# Dual_Drive_4.net
KiCad netlist of a schematic drawn in EAGLE
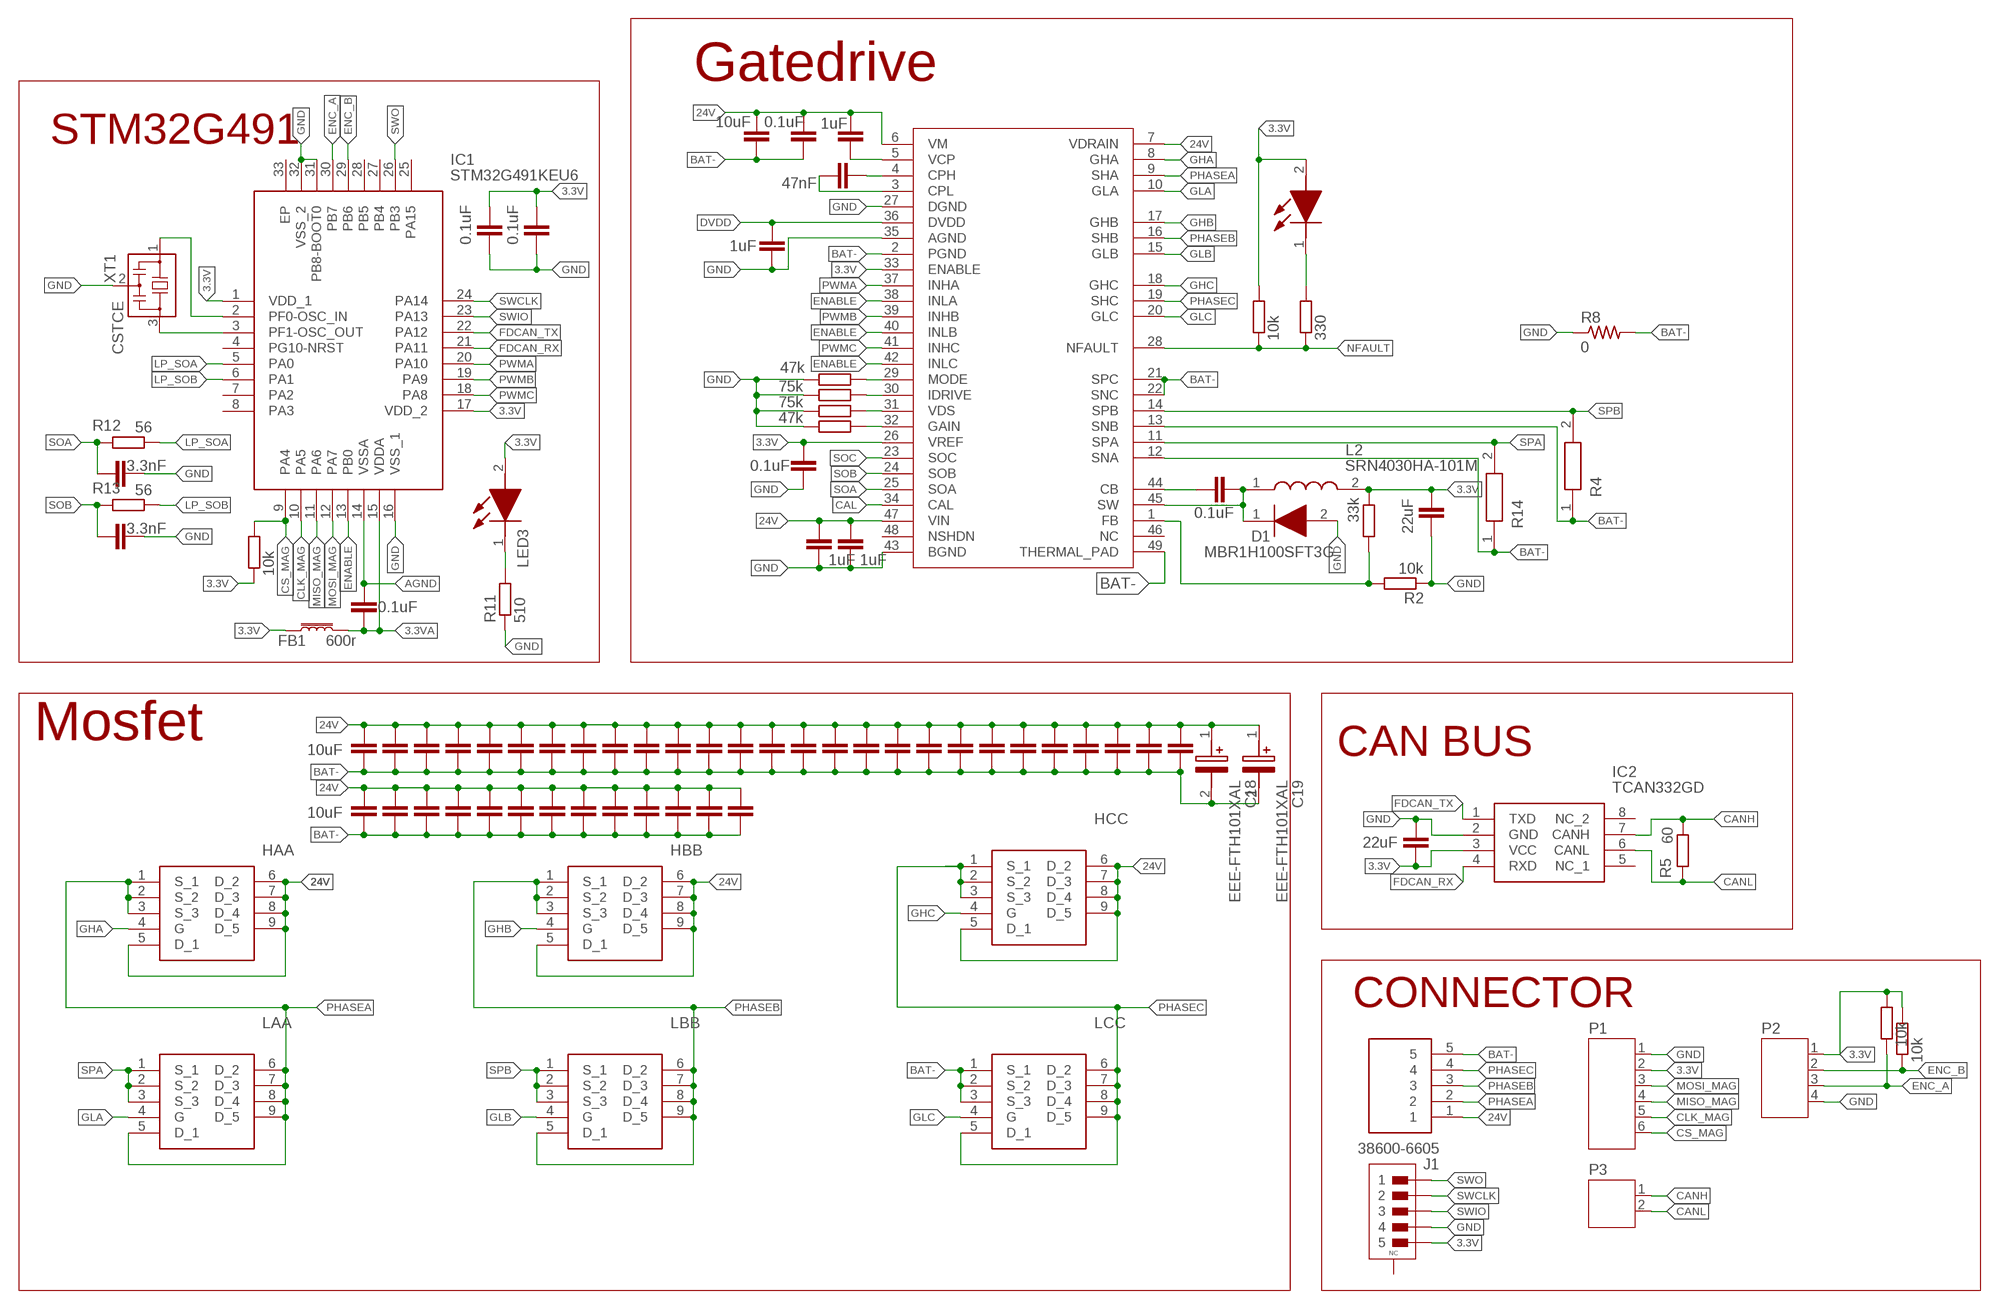
[diagram p0: schematic, sheet 1]

(export (version "E")
  (design (tool "Eeschema 10.0.6"))
  (components
    (comp (ref "C1")
      (value "3.3nF")
      (footprint "eagle-import:C0603")
      (libsource (lib "eagle-import") (part "rcl_334_C-EUC0603"))
    )
    (comp (ref "C2")
      (value "3.3nF")
      (footprint "eagle-import:C0603")
      (libsource (lib "eagle-import") (part "rcl_334_C-EUC0603"))
    )
    (comp (ref "C3")
      (value "10uF")
      (footprint "eagle-import:C1206")
      (libsource (lib "eagle-import") (part "C-EU1206C1206"))
    )
    (comp (ref "C4")
      (value "22uF")
      (footprint "eagle-import:C0603")
      (libsource (lib "eagle-import") (part "C-EUC0603"))
    )
    (comp (ref "C5")
      (value "10uF")
      (footprint "eagle-import:C1206")
      (libsource (lib "eagle-import") (part "C-EU1206C1206"))
    )
    (comp (ref "C6")
      (value "10uF")
      (footprint "eagle-import:C1206")
      (libsource (lib "eagle-import") (part "C-EU1206C1206"))
    )
    (comp (ref "C7")
      (value "10uF")
      (footprint "eagle-import:C1206")
      (libsource (lib "eagle-import") (part "C-EU1206C1206"))
    )
    (comp (ref "C8")
      (value "10uF")
      (footprint "eagle-import:C1206")
      (libsource (lib "eagle-import") (part "C-EU1206C1206"))
    )
    (comp (ref "C9")
      (value "10uF")
      (footprint "eagle-import:C1206")
      (libsource (lib "eagle-import") (part "C-EU1206C1206"))
    )
    (comp (ref "C10")
      (value "0.1uF")
      (footprint "eagle-import:C1206")
      (libsource (lib "eagle-import") (part "C-EU1206C1206"))
    )
    (comp (ref "C11")
      (value "1uF")
      (footprint "eagle-import:C0603")
      (libsource (lib "eagle-import") (part "C-EUC0603"))
    )
    (comp (ref "C12")
      (value "10uF")
      (footprint "eagle-import:C1206")
      (libsource (lib "eagle-import") (part "C-EU1206C1206"))
    )
    (comp (ref "C13")
      (value "0.1uF")
      (footprint "eagle-import:C0603")
      (libsource (lib "eagle-import") (part "C-EUC0603"))
    )
    (comp (ref "C14")
      (value "1uF")
      (footprint "eagle-import:C0603")
      (libsource (lib "eagle-import") (part "C-EUC0603"))
    )
    (comp (ref "C15")
      (value "0.1uF")
      (footprint "eagle-import:C0603")
      (libsource (lib "eagle-import") (part "C-EUC0603"))
    )
    (comp (ref "C16")
      (value "10uF")
      (footprint "eagle-import:C1206")
      (libsource (lib "eagle-import") (part "C-EU1206C1206"))
    )
    (comp (ref "C17")
      (value "10uF")
      (footprint "eagle-import:C1206")
      (libsource (lib "eagle-import") (part "C-EU1206C1206"))
    )
    (comp (ref "C18")
      (value "EEE-FTH101XAL")
      (footprint "eagle-import:EEEHP1H4R7P")
      (fields (field (name "MOUSER_PART_NUMBER") "667-EEE-FTH101XAL"))
      (libsource (lib "eagle-import") (part "EEE-FTH101XAL"))
    )
    (comp (ref "C19")
      (value "EEE-FTH101XAL")
      (footprint "eagle-import:EEEHP1H4R7P")
      (fields (field (name "MOUSER_PART_NUMBER") "667-EEE-FTH101XAL"))
      (libsource (lib "eagle-import") (part "EEE-FTH101XAL"))
    )
    (comp (ref "C20")
      (value "10uF")
      (footprint "eagle-import:C1206")
      (libsource (lib "eagle-import") (part "C-EU1206C1206"))
    )
    (comp (ref "C21")
      (value "10uF")
      (footprint "eagle-import:C1206")
      (libsource (lib "eagle-import") (part "C-EU1206C1206"))
    )
    (comp (ref "C22")
      (value "10uF")
      (footprint "eagle-import:C1206")
      (libsource (lib "eagle-import") (part "C-EU1206C1206"))
    )
    (comp (ref "C23")
      (value "10uF")
      (footprint "eagle-import:C1206")
      (libsource (lib "eagle-import") (part "C-EU1206C1206"))
    )
    (comp (ref "C24")
      (value "10uF")
      (footprint "eagle-import:C1206")
      (libsource (lib "eagle-import") (part "C-EU1206C1206"))
    )
    (comp (ref "C25")
      (value "10uF")
      (footprint "eagle-import:C1206")
      (libsource (lib "eagle-import") (part "C-EU1206C1206"))
    )
    (comp (ref "C26")
      (value "0.1uF")
      (footprint "eagle-import:C0603")
      (libsource (lib "eagle-import") (part "rcl_334_C-EUC0603"))
    )
    (comp (ref "C27")
      (value "0.1uF")
      (footprint "eagle-import:C0603")
      (libsource (lib "eagle-import") (part "rcl_334_C-EUC0603"))
    )
    (comp (ref "C28")
      (value "10uF")
      (footprint "eagle-import:C1206")
      (libsource (lib "eagle-import") (part "C-EU1206C1206"))
    )
    (comp (ref "C29")
      (value "10uF")
      (footprint "eagle-import:C1206")
      (libsource (lib "eagle-import") (part "C-EU1206C1206"))
    )
    (comp (ref "C30")
      (value "0.1uF")
      (footprint "eagle-import:C0603")
      (libsource (lib "eagle-import") (part "rcl_334_C-EUC0603"))
    )
    (comp (ref "C31")
      (value "10uF")
      (footprint "eagle-import:C1206")
      (libsource (lib "eagle-import") (part "C-EU1206C1206"))
    )
    (comp (ref "C32")
      (value "10uF")
      (footprint "eagle-import:C1206")
      (libsource (lib "eagle-import") (part "C-EU1206C1206"))
    )
    (comp (ref "C33")
      (value "10uF")
      (footprint "eagle-import:C1206")
      (libsource (lib "eagle-import") (part "C-EU1206C1206"))
    )
    (comp (ref "C34")
      (value "10uF")
      (footprint "eagle-import:C1206")
      (libsource (lib "eagle-import") (part "C-EU1206C1206"))
    )
    (comp (ref "C35")
      (value "10uF")
      (footprint "eagle-import:C1206")
      (libsource (lib "eagle-import") (part "C-EU1206C1206"))
    )
    (comp (ref "C36")
      (value "10uF")
      (footprint "eagle-import:C1206")
      (libsource (lib "eagle-import") (part "C-EU1206C1206"))
    )
    (comp (ref "C37")
      (value "10uF")
      (footprint "eagle-import:C1206")
      (libsource (lib "eagle-import") (part "C-EU1206C1206"))
    )
    (comp (ref "C38")
      (value "10uF")
      (footprint "eagle-import:C1206")
      (libsource (lib "eagle-import") (part "C-EU1206C1206"))
    )
    (comp (ref "C39")
      (value "10uF")
      (footprint "eagle-import:C1206")
      (libsource (lib "eagle-import") (part "C-EU1206C1206"))
    )
    (comp (ref "C40")
      (value "10uF")
      (footprint "eagle-import:C1206")
      (libsource (lib "eagle-import") (part "C-EU1206C1206"))
    )
    (comp (ref "C41")
      (value "10uF")
      (footprint "eagle-import:C1206")
      (libsource (lib "eagle-import") (part "C-EU1206C1206"))
    )
    (comp (ref "C42")
      (value "10uF")
      (footprint "eagle-import:C1206")
      (libsource (lib "eagle-import") (part "C-EU1206C1206"))
    )
    (comp (ref "C43")
      (value "10uF")
      (footprint "eagle-import:C1206")
      (libsource (lib "eagle-import") (part "C-EU1206C1206"))
    )
    (comp (ref "C44")
      (value "10uF")
      (footprint "eagle-import:C1206")
      (libsource (lib "eagle-import") (part "C-EU1206C1206"))
    )
    (comp (ref "C45")
      (value "47nF")
      (footprint "eagle-import:C0805")
      (libsource (lib "eagle-import") (part "C-EU0805C0805"))
    )
    (comp (ref "C46")
      (value "22uF")
      (footprint "eagle-import:C0603")
      (libsource (lib "eagle-import") (part "C-EUC0603"))
    )
    (comp (ref "C47")
      (value "10uF")
      (footprint "eagle-import:C1206")
      (libsource (lib "eagle-import") (part "C-EU1206C1206"))
    )
    (comp (ref "C48")
      (value "10uF")
      (footprint "eagle-import:C1206")
      (libsource (lib "eagle-import") (part "C-EU1206C1206"))
    )
    (comp (ref "C49")
      (value "10uF")
      (footprint "eagle-import:C1206")
      (libsource (lib "eagle-import") (part "C-EU1206C1206"))
    )
    (comp (ref "C50")
      (value "10uF")
      (footprint "eagle-import:C1206")
      (libsource (lib "eagle-import") (part "C-EU1206C1206"))
    )
    (comp (ref "C51")
      (value "10uF")
      (footprint "eagle-import:C1206")
      (libsource (lib "eagle-import") (part "C-EU1206C1206"))
    )
    (comp (ref "C52")
      (value "10uF")
      (footprint "eagle-import:C1206")
      (libsource (lib "eagle-import") (part "C-EU1206C1206"))
    )
    (comp (ref "C53")
      (value "10uF")
      (footprint "eagle-import:C1206")
      (libsource (lib "eagle-import") (part "C-EU1206C1206"))
    )
    (comp (ref "C54")
      (value "10uF")
      (footprint "eagle-import:C1206")
      (libsource (lib "eagle-import") (part "C-EU1206C1206"))
    )
    (comp (ref "C55")
      (value "10uF")
      (footprint "eagle-import:C1206")
      (libsource (lib "eagle-import") (part "C-EU1206C1206"))
    )
    (comp (ref "C56")
      (value "10uF")
      (footprint "eagle-import:C1206")
      (libsource (lib "eagle-import") (part "C-EU1206C1206"))
    )
    (comp (ref "CIN")
      (value "1uF")
      (footprint "eagle-import:C0603")
      (libsource (lib "eagle-import") (part "C-EUC0603"))
    )
    (comp (ref "CIN1")
      (value "1uF")
      (footprint "eagle-import:C0603")
      (libsource (lib "eagle-import") (part "C-EUC0603"))
    )
    (comp (ref "D1")
      (value "MBR1H100SFT3G")
      (footprint "eagle-import:SODFL3616X98N")
      (fields (field (name "MOUSER_PART_NUMBER") "863-MBR1H100SFT3G"))
      (libsource (lib "eagle-import") (part "MBR1H100SFT3G"))
    )
    (comp (ref "FB1")
      (value "600r")
      (footprint "eagle-import:0603")
      (libsource (lib "eagle-import") (part "FERRITE_BEAD-0603"))
    )
    (comp (ref "HAA")
      (value "TPH2R506PL,L1Q")
      (footprint "eagle-import:TPHR9003NLL1Q")
      (fields (field (name "MOUSER_PART_NUMBER") "757-TPH2R506PLL1Q"))
      (libsource (lib "eagle-import") (part "TPH2R506PL,L1Q"))
    )
    (comp (ref "HBB")
      (value "TPH2R506PL,L1Q")
      (footprint "eagle-import:TPHR9003NLL1Q")
      (fields (field (name "MOUSER_PART_NUMBER") "757-TPH2R506PLL1Q"))
      (libsource (lib "eagle-import") (part "TPH2R506PL,L1Q"))
    )
    (comp (ref "HCC")
      (value "TPH2R506PL,L1Q")
      (footprint "eagle-import:TPHR9003NLL1Q")
      (fields (field (name "MOUSER_PART_NUMBER") "757-TPH2R506PLL1Q"))
      (libsource (lib "eagle-import") (part "TPH2R506PL,L1Q"))
    )
    (comp (ref "IC1")
      (value "STM32G491KEU6")
      (footprint "eagle-import:QFN50P500X500X60-33N")
      (fields (field (name "MOUSER_PART_NUMBER") "511-STM32G491KEU6"))
      (libsource (lib "eagle-import") (part "STM32G491KEU6"))
    )
    (comp (ref "IC2")
      (value "TCAN332GD")
      (footprint "eagle-import:SOIC127P600X175-8N")
      (fields (field (name "MOUSER_PART_NUMBER") "595-TCAN332GD"))
      (libsource (lib "eagle-import") (part "TCAN332GD"))
    )
    (comp (ref "IC3")
      (value "DRV8323RHRGZR")
      (footprint "eagle-import:QFN50P700X700X100-49N")
      (fields (field (name "MOUSER_PART_NUMBER") "595-DRV8323RHRGZR"))
      (libsource (lib "eagle-import") (part "DRV8323RHRGZR"))
    )
    (comp (ref "J1")
      (value "38600-6605")
      (footprint "eagle-import:386006605")
      (fields (field (name "MOUSER_PART_NUMBER") "538-38600-6605"))
      (libsource (lib "eagle-import") (part "38600-6605"))
    )
    (comp (ref "L2")
      (value "SRN4030HA-101M")
      (footprint "eagle-import:SRN4030HA101M")
      (libsource (lib "eagle-import") (part "SRN4030HA-101M"))
    )
    (comp (ref "LAA")
      (value "TPH2R506PL,L1Q")
      (footprint "eagle-import:TPHR9003NLL1Q")
      (fields (field (name "MOUSER_PART_NUMBER") "757-TPH2R506PLL1Q"))
      (libsource (lib "eagle-import") (part "TPH2R506PL,L1Q"))
    )
    (comp (ref "LBB")
      (value "TPH2R506PL,L1Q")
      (footprint "eagle-import:TPHR9003NLL1Q")
      (fields (field (name "MOUSER_PART_NUMBER") "757-TPH2R506PLL1Q"))
      (libsource (lib "eagle-import") (part "TPH2R506PL,L1Q"))
    )
    (comp (ref "LCC")
      (value "TPH2R506PL,L1Q")
      (footprint "eagle-import:TPHR9003NLL1Q")
      (fields (field (name "MOUSER_PART_NUMBER") "757-TPH2R506PLL1Q"))
      (libsource (lib "eagle-import") (part "TPH2R506PL,L1Q"))
    )
    (comp (ref "LED1")
      (value "LTST-C191KRKT")
      (footprint "eagle-import:LEDC1608X55N")
      (fields (field (name "MOUSER_PART_NUMBER") "859-LTST-C191KRKT"))
      (libsource (lib "eagle-import") (part "LTST-C191KRKT"))
    )
    (comp (ref "LED3")
      (value "LTST-C191KRKT")
      (footprint "eagle-import:LEDC1608X55N")
      (fields (field (name "MOUSER_PART_NUMBER") "859-LTST-C191KRKT"))
      (libsource (lib "eagle-import") (part "LTST-C191KRKT"))
    )
    (comp (ref "P1")
      (value "JST-PH6")
      (footprint "eagle-import:JST-PH6")
      (libsource (lib "eagle-import") (part "JST-PH6"))
    )
    (comp (ref "P2")
      (value "JST-PH4")
      (footprint "eagle-import:JST-PH4")
      (libsource (lib "eagle-import") (part "JST-PH4"))
    )
    (comp (ref "P3")
      (value "JST-PH2")
      (footprint "eagle-import:JST-PH2")
      (libsource (lib "eagle-import") (part "JST-PH2"))
    )
    (comp (ref "R1")
      (value "33k")
      (footprint "eagle-import:R0603")
      (libsource (lib "eagle-import") (part "R-EU_R0603"))
    )
    (comp (ref "R2")
      (value "10k")
      (footprint "eagle-import:R0603")
      (libsource (lib "eagle-import") (part "R-EU_R0603"))
    )
    (comp (ref "R3")
      (value "47k")
      (footprint "eagle-import:R0603")
      (libsource (lib "eagle-import") (part "rcl_334_R-EU_R0603"))
    )
    (comp (ref "R4")
      (value "0.01")
      (footprint "eagle-import:RESC6434X90N")
      (fields
        (field (name "ARROW_PART_NUMBER") "CRA2512-FZ-R010ELF")
        (field (name "MOUSER_PART_NUMBER") "652-CRA2512FZR010ELF")
      )
      (libsource (lib "eagle-import") (part "CRA2512-FZ-R010ELF"))
    )
    (comp (ref "R5")
      (value "60")
      (footprint "eagle-import:R0603")
      (libsource (lib "eagle-import") (part "rcl_334_R-EU_R0603"))
    )
    (comp (ref "R6")
      (value "47k")
      (footprint "eagle-import:R0603")
      (libsource (lib "eagle-import") (part "rcl_334_R-EU_R0603"))
    )
    (comp (ref "R7")
      (value "75k")
      (footprint "eagle-import:R0603")
      (libsource (lib "eagle-import") (part "rcl_334_R-EU_R0603"))
    )
    (comp (ref "R8")
      (value "0")
      (footprint "eagle-import:M1206")
      (libsource (lib "eagle-import") (part "R-US_M1206"))
    )
    (comp (ref "R10")
      (value "75k")
      (footprint "eagle-import:R0603")
      (libsource (lib "eagle-import") (part "rcl_334_R-EU_R0603"))
    )
    (comp (ref "R11")
      (value "510")
      (footprint "eagle-import:R0603")
      (libsource (lib "eagle-import") (part "rcl_334_R-EU_R0603"))
    )
    (comp (ref "R12")
      (value "56")
      (footprint "eagle-import:R0603")
      (libsource (lib "eagle-import") (part "rcl_334_R-EU_R0603"))
    )
    (comp (ref "R13")
      (value "56")
      (footprint "eagle-import:R0603")
      (libsource (lib "eagle-import") (part "rcl_334_R-EU_R0603"))
    )
    (comp (ref "R14")
      (value "0.01")
      (footprint "eagle-import:RESC6434X90N")
      (fields
        (field (name "ARROW_PART_NUMBER") "CRA2512-FZ-R010ELF")
        (field (name "MOUSER_PART_NUMBER") "652-CRA2512FZR010ELF")
      )
      (libsource (lib "eagle-import") (part "CRA2512-FZ-R010ELF"))
    )
    (comp (ref "RPULL")
      (value "10k")
      (footprint "eagle-import:R0603")
      (libsource (lib "eagle-import") (part "R-EU_R0603"))
    )
    (comp (ref "RPULL1")
      (value "330")
      (footprint "eagle-import:R0603")
      (libsource (lib "eagle-import") (part "R-EU_R0603"))
    )
    (comp (ref "RPULL2")
      (value "10k")
      (footprint "eagle-import:R0603")
      (libsource (lib "eagle-import") (part "R-EU_R0603"))
    )
    (comp (ref "RPULL3")
      (value "10k")
      (footprint "eagle-import:R0603")
      (libsource (lib "eagle-import") (part "R-EU_R0603"))
    )
    (comp (ref "RPULL4")
      (value "10k")
      (footprint "eagle-import:R0603")
      (libsource (lib "eagle-import") (part "R-EU_R0603"))
    )
    (comp (ref "U$3")
      (value "CON-JST-PH2.0-5PIN-SMD")
      (footprint "eagle-import:CON-JST-PH2.0-5PIN-SMD")
      (libsource (lib "eagle-import") (part "CON-JST-PH2.0-5PIN-SMD"))
    )
    (comp (ref "XT1")
      (value "CSTCE")
      (footprint "eagle-import:CSTCE")
      (libsource (lib "eagle-import") (part "CSTCE"))
    )
  )
  (nets
    (net (code "1") (name "3.3V") (class "Default")
      (node (ref "C15") (pin "1") (pinfunction "1_1") (pintype "passive"))
      (node (ref "C26") (pin "1") (pinfunction "1_1") (pintype "passive"))
      (node (ref "C27") (pin "1") (pinfunction "1_1") (pintype "passive"))
      (node (ref "C4") (pin "2") (pinfunction "2_2") (pintype "passive"))
      (node (ref "C46") (pin "1") (pinfunction "1_1") (pintype "passive"))
      (node (ref "FB1") (pin "1") (pinfunction "1_1") (pintype "passive"))
      (node (ref "IC1") (pin "1") (pinfunction "VDD_1_1") (pintype "bidirectional"))
      (node (ref "IC1") (pin "17") (pinfunction "VDD_2_17") (pintype "bidirectional"))
      (node (ref "IC2") (pin "3") (pinfunction "VCC_3") (pintype "bidirectional"))
      (node (ref "IC3") (pin "26") (pinfunction "VREF_26") (pintype "bidirectional"))
      (node (ref "IC3") (pin "33") (pinfunction "ENABLE_33") (pintype "bidirectional"))
      (node (ref "L2") (pin "2") (pinfunction "2_2") (pintype "bidirectional"))
      (node (ref "LED1") (pin "2") (pinfunction "A_2") (pintype "bidirectional"))
      (node (ref "LED3") (pin "2") (pinfunction "A_2") (pintype "bidirectional"))
      (node (ref "P1") (pin "2") (pinfunction "2_2") (pintype "passive"))
      (node (ref "P2") (pin "1") (pinfunction "1_1") (pintype "passive"))
      (node (ref "R1") (pin "2") (pinfunction "2_2") (pintype "passive"))
      (node (ref "RPULL") (pin "2") (pinfunction "2_2") (pintype "passive"))
      (node (ref "RPULL2") (pin "1") (pinfunction "1_1") (pintype "passive"))
      (node (ref "RPULL3") (pin "2") (pinfunction "2_2") (pintype "passive"))
      (node (ref "RPULL4") (pin "2") (pinfunction "2_2") (pintype "passive"))
      (node (ref "U$3") (pin "5") (pinfunction "5_5") (pintype "bidirectional"))
    )
    (net (code "2") (name "3.3VA") (class "Default")
      (node (ref "C30") (pin "1") (pinfunction "1_1") (pintype "passive"))
      (node (ref "FB1") (pin "2") (pinfunction "2_2") (pintype "passive"))
      (node (ref "IC1") (pin "15") (pinfunction "VDDA_15") (pintype "bidirectional"))
    )
    (net (code "3") (name "24V") (class "Default")
      (node (ref "C10") (pin "1") (pinfunction "1_1") (pintype "passive"))
      (node (ref "C11") (pin "1") (pinfunction "1_1") (pintype "passive"))
      (node (ref "C12") (pin "1") (pinfunction "1_1") (pintype "passive"))
      (node (ref "C16") (pin "1") (pinfunction "1_1") (pintype "passive"))
      (node (ref "C17") (pin "1") (pinfunction "1_1") (pintype "passive"))
      (node (ref "C18") (pin "1") (pinfunction "+_1") (pintype "bidirectional"))
      (node (ref "C19") (pin "1") (pinfunction "+_1") (pintype "bidirectional"))
      (node (ref "C20") (pin "1") (pinfunction "1_1") (pintype "passive"))
      (node (ref "C21") (pin "1") (pinfunction "1_1") (pintype "passive"))
      (node (ref "C22") (pin "1") (pinfunction "1_1") (pintype "passive"))
      (node (ref "C23") (pin "1") (pinfunction "1_1") (pintype "passive"))
      (node (ref "C24") (pin "1") (pinfunction "1_1") (pintype "passive"))
      (node (ref "C25") (pin "1") (pinfunction "1_1") (pintype "passive"))
      (node (ref "C28") (pin "1") (pinfunction "1_1") (pintype "passive"))
      (node (ref "C29") (pin "1") (pinfunction "1_1") (pintype "passive"))
      (node (ref "C3") (pin "1") (pinfunction "1_1") (pintype "passive"))
      (node (ref "C31") (pin "1") (pinfunction "1_1") (pintype "passive"))
      (node (ref "C32") (pin "1") (pinfunction "1_1") (pintype "passive"))
      (node (ref "C33") (pin "1") (pinfunction "1_1") (pintype "passive"))
      (node (ref "C34") (pin "1") (pinfunction "1_1") (pintype "passive"))
      (node (ref "C35") (pin "1") (pinfunction "1_1") (pintype "passive"))
      (node (ref "C36") (pin "1") (pinfunction "1_1") (pintype "passive"))
      (node (ref "C37") (pin "1") (pinfunction "1_1") (pintype "passive"))
      (node (ref "C38") (pin "1") (pinfunction "1_1") (pintype "passive"))
      (node (ref "C39") (pin "1") (pinfunction "1_1") (pintype "passive"))
      (node (ref "C40") (pin "1") (pinfunction "1_1") (pintype "passive"))
      (node (ref "C41") (pin "1") (pinfunction "1_1") (pintype "passive"))
      (node (ref "C42") (pin "1") (pinfunction "1_1") (pintype "passive"))
      (node (ref "C43") (pin "1") (pinfunction "1_1") (pintype "passive"))
      (node (ref "C44") (pin "1") (pinfunction "1_1") (pintype "passive"))
      (node (ref "C47") (pin "1") (pinfunction "1_1") (pintype "passive"))
      (node (ref "C48") (pin "1") (pinfunction "1_1") (pintype "passive"))
      (node (ref "C49") (pin "1") (pinfunction "1_1") (pintype "passive"))
      (node (ref "C5") (pin "1") (pinfunction "1_1") (pintype "passive"))
      (node (ref "C50") (pin "1") (pinfunction "1_1") (pintype "passive"))
      (node (ref "C51") (pin "1") (pinfunction "1_1") (pintype "passive"))
      (node (ref "C52") (pin "1") (pinfunction "1_1") (pintype "passive"))
      (node (ref "C53") (pin "1") (pinfunction "1_1") (pintype "passive"))
      (node (ref "C54") (pin "1") (pinfunction "1_1") (pintype "passive"))
      (node (ref "C55") (pin "1") (pinfunction "1_1") (pintype "passive"))
      (node (ref "C56") (pin "1") (pinfunction "1_1") (pintype "passive"))
      (node (ref "C6") (pin "1") (pinfunction "1_1") (pintype "passive"))
      (node (ref "C7") (pin "1") (pinfunction "1_1") (pintype "passive"))
      (node (ref "C8") (pin "1") (pinfunction "1_1") (pintype "passive"))
      (node (ref "C9") (pin "1") (pinfunction "1_1") (pintype "passive"))
      (node (ref "CIN") (pin "1") (pinfunction "1_1") (pintype "passive"))
      (node (ref "CIN1") (pin "1") (pinfunction "1_1") (pintype "passive"))
      (node (ref "HAA") (pin "5") (pinfunction "D_1_5") (pintype "bidirectional"))
      (node (ref "HAA") (pin "6") (pinfunction "D_2_6") (pintype "bidirectional"))
      (node (ref "HAA") (pin "7") (pinfunction "D_3_7") (pintype "bidirectional"))
      (node (ref "HAA") (pin "8") (pinfunction "D_4_8") (pintype "bidirectional"))
      (node (ref "HAA") (pin "9") (pinfunction "D_5_9") (pintype "bidirectional"))
      (node (ref "HBB") (pin "5") (pinfunction "D_1_5") (pintype "bidirectional"))
      (node (ref "HBB") (pin "6") (pinfunction "D_2_6") (pintype "bidirectional"))
      (node (ref "HBB") (pin "7") (pinfunction "D_3_7") (pintype "bidirectional"))
      (node (ref "HBB") (pin "8") (pinfunction "D_4_8") (pintype "bidirectional"))
      (node (ref "HBB") (pin "9") (pinfunction "D_5_9") (pintype "bidirectional"))
      (node (ref "HCC") (pin "5") (pinfunction "D_1_5") (pintype "bidirectional"))
      (node (ref "HCC") (pin "6") (pinfunction "D_2_6") (pintype "bidirectional"))
      (node (ref "HCC") (pin "7") (pinfunction "D_3_7") (pintype "bidirectional"))
      (node (ref "HCC") (pin "8") (pinfunction "D_4_8") (pintype "bidirectional"))
      (node (ref "HCC") (pin "9") (pinfunction "D_5_9") (pintype "bidirectional"))
      (node (ref "IC3") (pin "47") (pinfunction "VIN_47") (pintype "bidirectional"))
      (node (ref "IC3") (pin "6") (pinfunction "VM_6") (pintype "bidirectional"))
      (node (ref "IC3") (pin "7") (pinfunction "VDRAIN_7") (pintype "bidirectional"))
      (node (ref "J1") (pin "1") (pinfunction "1_1") (pintype "bidirectional"))
    )
    (net (code "4") (name "AGND") (class "Default")
      (node (ref "C30") (pin "2") (pinfunction "2_2") (pintype "passive"))
      (node (ref "IC1") (pin "14") (pinfunction "VSSA_14") (pintype "bidirectional"))
    )
    (net (code "5") (name "BAT-") (class "Default")
      (node (ref "C10") (pin "2") (pinfunction "2_2") (pintype "passive"))
      (node (ref "C12") (pin "2") (pinfunction "2_2") (pintype "passive"))
      (node (ref "C16") (pin "2") (pinfunction "2_2") (pintype "passive"))
      (node (ref "C17") (pin "2") (pinfunction "2_2") (pintype "passive"))
      (node (ref "C18") (pin "2") (pinfunction "-_2") (pintype "bidirectional"))
      (node (ref "C19") (pin "2") (pinfunction "-_2") (pintype "bidirectional"))
      (node (ref "C20") (pin "2") (pinfunction "2_2") (pintype "passive"))
      (node (ref "C21") (pin "2") (pinfunction "2_2") (pintype "passive"))
      (node (ref "C22") (pin "2") (pinfunction "2_2") (pintype "passive"))
      (node (ref "C23") (pin "2") (pinfunction "2_2") (pintype "passive"))
      (node (ref "C24") (pin "2") (pinfunction "2_2") (pintype "passive"))
      (node (ref "C25") (pin "2") (pinfunction "2_2") (pintype "passive"))
      (node (ref "C28") (pin "2") (pinfunction "2_2") (pintype "passive"))
      (node (ref "C29") (pin "2") (pinfunction "2_2") (pintype "passive"))
      (node (ref "C3") (pin "2") (pinfunction "2_2") (pintype "passive"))
      (node (ref "C31") (pin "2") (pinfunction "2_2") (pintype "passive"))
      (node (ref "C32") (pin "2") (pinfunction "2_2") (pintype "passive"))
      (node (ref "C33") (pin "2") (pinfunction "2_2") (pintype "passive"))
      (node (ref "C34") (pin "2") (pinfunction "2_2") (pintype "passive"))
      (node (ref "C35") (pin "2") (pinfunction "2_2") (pintype "passive"))
      (node (ref "C36") (pin "2") (pinfunction "2_2") (pintype "passive"))
      (node (ref "C37") (pin "2") (pinfunction "2_2") (pintype "passive"))
      (node (ref "C38") (pin "2") (pinfunction "2_2") (pintype "passive"))
      (node (ref "C39") (pin "2") (pinfunction "2_2") (pintype "passive"))
      (node (ref "C40") (pin "2") (pinfunction "2_2") (pintype "passive"))
      (node (ref "C41") (pin "2") (pinfunction "2_2") (pintype "passive"))
      (node (ref "C42") (pin "2") (pinfunction "2_2") (pintype "passive"))
      (node (ref "C43") (pin "2") (pinfunction "2_2") (pintype "passive"))
      (node (ref "C44") (pin "2") (pinfunction "2_2") (pintype "passive"))
      (node (ref "C47") (pin "2") (pinfunction "2_2") (pintype "passive"))
      (node (ref "C48") (pin "2") (pinfunction "2_2") (pintype "passive"))
      (node (ref "C49") (pin "2") (pinfunction "2_2") (pintype "passive"))
      (node (ref "C5") (pin "2") (pinfunction "2_2") (pintype "passive"))
      (node (ref "C50") (pin "2") (pinfunction "2_2") (pintype "passive"))
      (node (ref "C51") (pin "2") (pinfunction "2_2") (pintype "passive"))
      (node (ref "C52") (pin "2") (pinfunction "2_2") (pintype "passive"))
      (node (ref "C53") (pin "2") (pinfunction "2_2") (pintype "passive"))
      (node (ref "C54") (pin "2") (pinfunction "2_2") (pintype "passive"))
      (node (ref "C55") (pin "2") (pinfunction "2_2") (pintype "passive"))
      (node (ref "C56") (pin "2") (pinfunction "2_2") (pintype "passive"))
      (node (ref "C6") (pin "2") (pinfunction "2_2") (pintype "passive"))
      (node (ref "C7") (pin "2") (pinfunction "2_2") (pintype "passive"))
      (node (ref "C8") (pin "2") (pinfunction "2_2") (pintype "passive"))
      (node (ref "C9") (pin "2") (pinfunction "2_2") (pintype "passive"))
      (node (ref "IC3") (pin "12") (pinfunction "SNA_12") (pintype "bidirectional"))
      (node (ref "IC3") (pin "13") (pinfunction "SNB_13") (pintype "bidirectional"))
      (node (ref "IC3") (pin "2") (pinfunction "PGND_2") (pintype "bidirectional"))
      (node (ref "IC3") (pin "21") (pinfunction "SPC_21") (pintype "bidirectional"))
      (node (ref "IC3") (pin "22") (pinfunction "SNC_22") (pintype "bidirectional"))
      (node (ref "IC3") (pin "49") (pinfunction "THERMAL_PAD_49") (pintype "bidirectional"))
      (node (ref "J1") (pin "5") (pinfunction "5_5") (pintype "bidirectional"))
      (node (ref "LCC") (pin "1") (pinfunction "S_1_1") (pintype "bidirectional"))
      (node (ref "LCC") (pin "2") (pinfunction "S_2_2") (pintype "bidirectional"))
      (node (ref "LCC") (pin "3") (pinfunction "S_3_3") (pintype "bidirectional"))
      (node (ref "R14") (pin "1") (pinfunction "1_1") (pintype "bidirectional"))
      (node (ref "R4") (pin "1") (pinfunction "1_1") (pintype "bidirectional"))
      (node (ref "R8") (pin "2") (pinfunction "2_2") (pintype "passive"))
    )
    (net (code "6") (name "CAL") (class "Default")
      (node (ref "IC3") (pin "34") (pinfunction "CAL_34") (pintype "bidirectional"))
    )
    (net (code "7") (name "CANH") (class "Default")
      (node (ref "IC2") (pin "7") (pinfunction "CANH_7") (pintype "bidirectional"))
      (node (ref "P3") (pin "1") (pinfunction "1_1") (pintype "passive"))
      (node (ref "R5") (pin "1") (pinfunction "1_1") (pintype "passive"))
    )
    (net (code "8") (name "CANL") (class "Default")
      (node (ref "IC2") (pin "6") (pinfunction "CANL_6") (pintype "bidirectional"))
      (node (ref "P3") (pin "2") (pinfunction "2_2") (pintype "passive"))
      (node (ref "R5") (pin "2") (pinfunction "2_2") (pintype "passive"))
    )
    (net (code "9") (name "CLK_MAG") (class "Default")
      (node (ref "IC1") (pin "10") (pinfunction "PA5_10") (pintype "bidirectional"))
      (node (ref "P1") (pin "5") (pinfunction "5_5") (pintype "passive"))
    )
    (net (code "10") (name "CS_MAG") (class "Default")
      (node (ref "IC1") (pin "9") (pinfunction "PA4_9") (pintype "bidirectional"))
      (node (ref "P1") (pin "6") (pinfunction "6_6") (pintype "passive"))
      (node (ref "RPULL2") (pin "2") (pinfunction "2_2") (pintype "passive"))
    )
    (net (code "11") (name "DVDD") (class "Default")
      (node (ref "C14") (pin "1") (pinfunction "1_1") (pintype "passive"))
      (node (ref "IC3") (pin "36") (pinfunction "DVDD_36") (pintype "bidirectional"))
    )
    (net (code "12") (name "ENABLE") (class "Default")
      (node (ref "IC1") (pin "13") (pinfunction "PB0_13") (pintype "bidirectional"))
      (node (ref "IC3") (pin "38") (pinfunction "INLA_38") (pintype "bidirectional"))
      (node (ref "IC3") (pin "40") (pinfunction "INLB_40") (pintype "bidirectional"))
      (node (ref "IC3") (pin "42") (pinfunction "INLC_42") (pintype "bidirectional"))
    )
    (net (code "13") (name "ENC_A") (class "Default")
      (node (ref "IC1") (pin "30") (pinfunction "PB7_30") (pintype "bidirectional"))
      (node (ref "P2") (pin "3") (pinfunction "3_3") (pintype "passive"))
      (node (ref "RPULL4") (pin "1") (pinfunction "1_1") (pintype "passive"))
    )
    (net (code "14") (name "ENC_B") (class "Default")
      (node (ref "IC1") (pin "29") (pinfunction "PB6_29") (pintype "bidirectional"))
      (node (ref "P2") (pin "2") (pinfunction "2_2") (pintype "passive"))
      (node (ref "RPULL3") (pin "1") (pinfunction "1_1") (pintype "passive"))
    )
    (net (code "15") (name "FDCAN_RX") (class "Default")
      (node (ref "IC1") (pin "21") (pinfunction "PA11_21") (pintype "bidirectional"))
      (node (ref "IC2") (pin "4") (pinfunction "RXD_4") (pintype "bidirectional"))
    )
    (net (code "16") (name "FDCAN_TX") (class "Default")
      (node (ref "IC1") (pin "22") (pinfunction "PA12_22") (pintype "bidirectional"))
      (node (ref "IC2") (pin "1") (pinfunction "TXD_1") (pintype "bidirectional"))
    )
    (net (code "17") (name "GHA") (class "Default")
      (node (ref "HAA") (pin "4") (pinfunction "G_4") (pintype "bidirectional"))
      (node (ref "IC3") (pin "8") (pinfunction "GHA_8") (pintype "bidirectional"))
    )
    (net (code "18") (name "GHB") (class "Default")
      (node (ref "HBB") (pin "4") (pinfunction "G_4") (pintype "bidirectional"))
      (node (ref "IC3") (pin "17") (pinfunction "GHB_17") (pintype "bidirectional"))
    )
    (net (code "19") (name "GHC") (class "Default")
      (node (ref "HCC") (pin "4") (pinfunction "G_4") (pintype "bidirectional"))
      (node (ref "IC3") (pin "18") (pinfunction "GHC_18") (pintype "bidirectional"))
    )
    (net (code "20") (name "GLA") (class "Default")
      (node (ref "IC3") (pin "10") (pinfunction "GLA_10") (pintype "bidirectional"))
      (node (ref "LAA") (pin "4") (pinfunction "G_4") (pintype "bidirectional"))
    )
    (net (code "21") (name "GLB") (class "Default")
      (node (ref "IC3") (pin "15") (pinfunction "GLB_15") (pintype "bidirectional"))
      (node (ref "LBB") (pin "4") (pinfunction "G_4") (pintype "bidirectional"))
    )
    (net (code "22") (name "GLC") (class "Default")
      (node (ref "IC3") (pin "20") (pinfunction "GLC_20") (pintype "bidirectional"))
      (node (ref "LCC") (pin "4") (pinfunction "G_4") (pintype "bidirectional"))
    )
    (net (code "23") (name "GND") (class "Default")
      (node (ref "C1") (pin "2") (pinfunction "2_2") (pintype "passive"))
      (node (ref "C14") (pin "2") (pinfunction "2_2") (pintype "passive"))
      (node (ref "C15") (pin "2") (pinfunction "2_2") (pintype "passive"))
      (node (ref "C2") (pin "2") (pinfunction "2_2") (pintype "passive"))
      (node (ref "C26") (pin "2") (pinfunction "2_2") (pintype "passive"))
      (node (ref "C27") (pin "2") (pinfunction "2_2") (pintype "passive"))
      (node (ref "C4") (pin "1") (pinfunction "1_1") (pintype "passive"))
      (node (ref "C46") (pin "2") (pinfunction "2_2") (pintype "passive"))
      (node (ref "CIN") (pin "2") (pinfunction "2_2") (pintype "passive"))
      (node (ref "CIN1") (pin "2") (pinfunction "2_2") (pintype "passive"))
      (node (ref "D1") (pin "2") (pinfunction "A_2") (pintype "bidirectional"))
      (node (ref "IC1") (pin "16") (pinfunction "VSS_1_16") (pintype "bidirectional"))
      (node (ref "IC1") (pin "31") (pinfunction "PB8-BOOT0_31") (pintype "bidirectional"))
      (node (ref "IC1") (pin "32") (pinfunction "VSS_2_32") (pintype "bidirectional"))
      (node (ref "IC2") (pin "2") (pinfunction "GND_2") (pintype "bidirectional"))
      (node (ref "IC3") (pin "27") (pinfunction "DGND_27") (pintype "bidirectional"))
      (node (ref "IC3") (pin "35") (pinfunction "AGND_35") (pintype "bidirectional"))
      (node (ref "IC3") (pin "43") (pinfunction "BGND_43") (pintype "bidirectional"))
      (node (ref "P1") (pin "1") (pinfunction "1_1") (pintype "passive"))
      (node (ref "P2") (pin "4") (pinfunction "4_4") (pintype "passive"))
      (node (ref "R10") (pin "1") (pinfunction "1_1") (pintype "passive"))
      (node (ref "R11") (pin "1") (pinfunction "1_1") (pintype "passive"))
      (node (ref "R2") (pin "1") (pinfunction "1_1") (pintype "passive"))
      (node (ref "R3") (pin "1") (pinfunction "1_1") (pintype "passive"))
      (node (ref "R6") (pin "1") (pinfunction "1_1") (pintype "passive"))
      (node (ref "R7") (pin "1") (pinfunction "1_1") (pintype "passive"))
      (node (ref "R8") (pin "1") (pinfunction "1_1") (pintype "passive"))
      (node (ref "U$3") (pin "4") (pinfunction "4_4") (pintype "bidirectional"))
      (node (ref "XT1") (pin "2") (pinfunction "2_2") (pintype "passive"))
    )
    (net (code "24") (name "LP_SOA") (class "Default")
      (node (ref "IC1") (pin "5") (pinfunction "PA0_5") (pintype "bidirectional"))
      (node (ref "R12") (pin "1") (pinfunction "1_1") (pintype "passive"))
    )
    (net (code "25") (name "LP_SOB") (class "Default")
      (node (ref "IC1") (pin "6") (pinfunction "PA1_6") (pintype "bidirectional"))
      (node (ref "R13") (pin "1") (pinfunction "1_1") (pintype "passive"))
    )
    (net (code "26") (name "MISO_MAG") (class "Default")
      (node (ref "IC1") (pin "11") (pinfunction "PA6_11") (pintype "bidirectional"))
      (node (ref "P1") (pin "4") (pinfunction "4_4") (pintype "passive"))
    )
    (net (code "27") (name "MOSI_MAG") (class "Default")
      (node (ref "IC1") (pin "12") (pinfunction "PA7_12") (pintype "bidirectional"))
      (node (ref "P1") (pin "3") (pinfunction "3_3") (pintype "passive"))
    )
    (net (code "28") (name "NFAULT") (class "Default")
      (node (ref "IC3") (pin "28") (pinfunction "NFAULT_28") (pintype "bidirectional"))
      (node (ref "RPULL") (pin "1") (pinfunction "1_1") (pintype "passive"))
      (node (ref "RPULL1") (pin "1") (pinfunction "1_1") (pintype "passive"))
    )
    (net (code "29") (name "Net-(D1-K)") (class "Default")
      (node (ref "C13") (pin "2") (pinfunction "2_2") (pintype "passive"))
      (node (ref "D1") (pin "1") (pinfunction "K_1") (pintype "bidirectional"))
      (node (ref "IC3") (pin "45") (pinfunction "SW_45") (pintype "bidirectional"))
      (node (ref "L2") (pin "1") (pinfunction "1_1") (pintype "bidirectional"))
    )
    (net (code "30") (name "Net-(IC1-PF0-OSC_IN)") (class "Default")
      (node (ref "IC1") (pin "2") (pinfunction "PF0-OSC_IN_2") (pintype "bidirectional"))
      (node (ref "XT1") (pin "1") (pinfunction "1_1") (pintype "passive"))
    )
    (net (code "31") (name "Net-(IC1-PF1-OSC_OUT)") (class "Default")
      (node (ref "IC1") (pin "3") (pinfunction "PF1-OSC_OUT_3") (pintype "bidirectional"))
      (node (ref "XT1") (pin "3") (pinfunction "3_3") (pintype "passive"))
    )
    (net (code "32") (name "Net-(IC3-CB)") (class "Default")
      (node (ref "C13") (pin "1") (pinfunction "1_1") (pintype "passive"))
      (node (ref "IC3") (pin "44") (pinfunction "CB_44") (pintype "bidirectional"))
    )
    (net (code "33") (name "Net-(IC3-CPH)") (class "Default")
      (node (ref "C45") (pin "2") (pinfunction "2_2") (pintype "passive"))
      (node (ref "IC3") (pin "4") (pinfunction "CPH_4") (pintype "bidirectional"))
    )
    (net (code "34") (name "Net-(IC3-CPL)") (class "Default")
      (node (ref "C45") (pin "1") (pinfunction "1_1") (pintype "passive"))
      (node (ref "IC3") (pin "3") (pinfunction "CPL_3") (pintype "bidirectional"))
    )
    (net (code "35") (name "Net-(IC3-FB)") (class "Default")
      (node (ref "IC3") (pin "1") (pinfunction "FB_1") (pintype "bidirectional"))
      (node (ref "R1") (pin "1") (pinfunction "1_1") (pintype "passive"))
      (node (ref "R2") (pin "2") (pinfunction "2_2") (pintype "passive"))
    )
    (net (code "36") (name "Net-(IC3-GAIN)") (class "Default")
      (node (ref "IC3") (pin "32") (pinfunction "GAIN_32") (pintype "bidirectional"))
      (node (ref "R3") (pin "2") (pinfunction "2_2") (pintype "passive"))
    )
    (net (code "37") (name "Net-(IC3-IDRIVE)") (class "Default")
      (node (ref "IC3") (pin "30") (pinfunction "IDRIVE_30") (pintype "bidirectional"))
      (node (ref "R7") (pin "2") (pinfunction "2_2") (pintype "passive"))
    )
    (net (code "38") (name "Net-(IC3-MODE)") (class "Default")
      (node (ref "IC3") (pin "29") (pinfunction "MODE_29") (pintype "bidirectional"))
      (node (ref "R6") (pin "2") (pinfunction "2_2") (pintype "passive"))
    )
    (net (code "39") (name "Net-(IC3-VCP)") (class "Default")
      (node (ref "C11") (pin "2") (pinfunction "2_2") (pintype "passive"))
      (node (ref "IC3") (pin "5") (pinfunction "VCP_5") (pintype "bidirectional"))
    )
    (net (code "40") (name "Net-(IC3-VDS)") (class "Default")
      (node (ref "IC3") (pin "31") (pinfunction "VDS_31") (pintype "bidirectional"))
      (node (ref "R10") (pin "2") (pinfunction "2_2") (pintype "passive"))
    )
    (net (code "41") (name "Net-(LED1-K)") (class "Default")
      (node (ref "LED1") (pin "1") (pinfunction "K_1") (pintype "bidirectional"))
      (node (ref "RPULL1") (pin "2") (pinfunction "2_2") (pintype "passive"))
    )
    (net (code "42") (name "Net-(LED3-K)") (class "Default")
      (node (ref "LED3") (pin "1") (pinfunction "K_1") (pintype "bidirectional"))
      (node (ref "R11") (pin "2") (pinfunction "2_2") (pintype "passive"))
    )
    (net (code "43") (name "PHASEA") (class "Default")
      (node (ref "HAA") (pin "1") (pinfunction "S_1_1") (pintype "bidirectional"))
      (node (ref "HAA") (pin "2") (pinfunction "S_2_2") (pintype "bidirectional"))
      (node (ref "HAA") (pin "3") (pinfunction "S_3_3") (pintype "bidirectional"))
      (node (ref "IC3") (pin "9") (pinfunction "SHA_9") (pintype "bidirectional"))
      (node (ref "J1") (pin "2") (pinfunction "2_2") (pintype "bidirectional"))
      (node (ref "LAA") (pin "5") (pinfunction "D_1_5") (pintype "bidirectional"))
      (node (ref "LAA") (pin "6") (pinfunction "D_2_6") (pintype "bidirectional"))
      (node (ref "LAA") (pin "7") (pinfunction "D_3_7") (pintype "bidirectional"))
      (node (ref "LAA") (pin "8") (pinfunction "D_4_8") (pintype "bidirectional"))
      (node (ref "LAA") (pin "9") (pinfunction "D_5_9") (pintype "bidirectional"))
    )
    (net (code "44") (name "PHASEB") (class "Default")
      (node (ref "HBB") (pin "1") (pinfunction "S_1_1") (pintype "bidirectional"))
      (node (ref "HBB") (pin "2") (pinfunction "S_2_2") (pintype "bidirectional"))
      (node (ref "HBB") (pin "3") (pinfunction "S_3_3") (pintype "bidirectional"))
      (node (ref "IC3") (pin "16") (pinfunction "SHB_16") (pintype "bidirectional"))
      (node (ref "J1") (pin "3") (pinfunction "3_3") (pintype "bidirectional"))
      (node (ref "LBB") (pin "5") (pinfunction "D_1_5") (pintype "bidirectional"))
      (node (ref "LBB") (pin "6") (pinfunction "D_2_6") (pintype "bidirectional"))
      (node (ref "LBB") (pin "7") (pinfunction "D_3_7") (pintype "bidirectional"))
      (node (ref "LBB") (pin "8") (pinfunction "D_4_8") (pintype "bidirectional"))
      (node (ref "LBB") (pin "9") (pinfunction "D_5_9") (pintype "bidirectional"))
    )
    (net (code "45") (name "PHASEC") (class "Default")
      (node (ref "HCC") (pin "1") (pinfunction "S_1_1") (pintype "bidirectional"))
      (node (ref "HCC") (pin "2") (pinfunction "S_2_2") (pintype "bidirectional"))
      (node (ref "HCC") (pin "3") (pinfunction "S_3_3") (pintype "bidirectional"))
      (node (ref "IC3") (pin "19") (pinfunction "SHC_19") (pintype "bidirectional"))
      (node (ref "J1") (pin "4") (pinfunction "4_4") (pintype "bidirectional"))
      (node (ref "LCC") (pin "5") (pinfunction "D_1_5") (pintype "bidirectional"))
      (node (ref "LCC") (pin "6") (pinfunction "D_2_6") (pintype "bidirectional"))
      (node (ref "LCC") (pin "7") (pinfunction "D_3_7") (pintype "bidirectional"))
      (node (ref "LCC") (pin "8") (pinfunction "D_4_8") (pintype "bidirectional"))
      (node (ref "LCC") (pin "9") (pinfunction "D_5_9") (pintype "bidirectional"))
    )
    (net (code "46") (name "PWMA") (class "Default")
      (node (ref "IC1") (pin "20") (pinfunction "PA10_20") (pintype "bidirectional"))
      (node (ref "IC3") (pin "37") (pinfunction "INHA_37") (pintype "bidirectional"))
    )
    (net (code "47") (name "PWMB") (class "Default")
      (node (ref "IC1") (pin "19") (pinfunction "PA9_19") (pintype "bidirectional"))
      (node (ref "IC3") (pin "39") (pinfunction "INHB_39") (pintype "bidirectional"))
    )
    (net (code "48") (name "PWMC") (class "Default")
      (node (ref "IC1") (pin "18") (pinfunction "PA8_18") (pintype "bidirectional"))
      (node (ref "IC3") (pin "41") (pinfunction "INHC_41") (pintype "bidirectional"))
    )
    (net (code "49") (name "SOA") (class "Default")
      (node (ref "C1") (pin "1") (pinfunction "1_1") (pintype "passive"))
      (node (ref "IC3") (pin "25") (pinfunction "SOA_25") (pintype "bidirectional"))
      (node (ref "R12") (pin "2") (pinfunction "2_2") (pintype "passive"))
    )
    (net (code "50") (name "SOB") (class "Default")
      (node (ref "C2") (pin "1") (pinfunction "1_1") (pintype "passive"))
      (node (ref "IC3") (pin "24") (pinfunction "SOB_24") (pintype "bidirectional"))
      (node (ref "R13") (pin "2") (pinfunction "2_2") (pintype "passive"))
    )
    (net (code "51") (name "SOC") (class "Default")
      (node (ref "IC3") (pin "23") (pinfunction "SOC_23") (pintype "bidirectional"))
    )
    (net (code "52") (name "SPA") (class "Default")
      (node (ref "IC3") (pin "11") (pinfunction "SPA_11") (pintype "bidirectional"))
      (node (ref "LAA") (pin "1") (pinfunction "S_1_1") (pintype "bidirectional"))
      (node (ref "LAA") (pin "2") (pinfunction "S_2_2") (pintype "bidirectional"))
      (node (ref "LAA") (pin "3") (pinfunction "S_3_3") (pintype "bidirectional"))
      (node (ref "R14") (pin "2") (pinfunction "2_2") (pintype "bidirectional"))
    )
    (net (code "53") (name "SPB") (class "Default")
      (node (ref "IC3") (pin "14") (pinfunction "SPB_14") (pintype "bidirectional"))
      (node (ref "LBB") (pin "1") (pinfunction "S_1_1") (pintype "bidirectional"))
      (node (ref "LBB") (pin "2") (pinfunction "S_2_2") (pintype "bidirectional"))
      (node (ref "LBB") (pin "3") (pinfunction "S_3_3") (pintype "bidirectional"))
      (node (ref "R4") (pin "2") (pinfunction "2_2") (pintype "bidirectional"))
    )
    (net (code "54") (name "SWCLK") (class "Default")
      (node (ref "IC1") (pin "24") (pinfunction "PA14_24") (pintype "bidirectional"))
      (node (ref "U$3") (pin "2") (pinfunction "2_2") (pintype "bidirectional"))
    )
    (net (code "55") (name "SWIO") (class "Default")
      (node (ref "IC1") (pin "23") (pinfunction "PA13_23") (pintype "bidirectional"))
      (node (ref "U$3") (pin "3") (pinfunction "3_3") (pintype "bidirectional"))
    )
    (net (code "56") (name "SWO") (class "Default")
      (node (ref "IC1") (pin "26") (pinfunction "PB3_26") (pintype "bidirectional"))
      (node (ref "U$3") (pin "1") (pinfunction "1_1") (pintype "bidirectional"))
    )
    (net (code "57") (name "unconnected-(IC1-EP-Pad33)") (class "Default")
      (node (ref "IC1") (pin "33") (pinfunction "EP_33") (pintype "bidirectional"))
    )
    (net (code "58") (name "unconnected-(IC1-PA2-Pad7)") (class "Default")
      (node (ref "IC1") (pin "7") (pinfunction "PA2_7") (pintype "bidirectional"))
    )
    (net (code "59") (name "unconnected-(IC1-PA3-Pad8)") (class "Default")
      (node (ref "IC1") (pin "8") (pinfunction "PA3_8") (pintype "bidirectional"))
    )
    (net (code "60") (name "unconnected-(IC1-PA15-Pad25)") (class "Default")
      (node (ref "IC1") (pin "25") (pinfunction "PA15_25") (pintype "bidirectional"))
    )
    (net (code "61") (name "unconnected-(IC1-PB4-Pad27)") (class "Default")
      (node (ref "IC1") (pin "27") (pinfunction "PB4_27") (pintype "bidirectional"))
    )
    (net (code "62") (name "unconnected-(IC1-PB5-Pad28)") (class "Default")
      (node (ref "IC1") (pin "28") (pinfunction "PB5_28") (pintype "bidirectional"))
    )
    (net (code "63") (name "unconnected-(IC1-PG10-NRST-Pad4)") (class "Default")
      (node (ref "IC1") (pin "4") (pinfunction "PG10-NRST_4") (pintype "bidirectional"))
    )
    (net (code "64") (name "unconnected-(IC2-NC_1-Pad5)") (class "Default")
      (node (ref "IC2") (pin "5") (pinfunction "NC_1_5") (pintype "bidirectional"))
    )
    (net (code "65") (name "unconnected-(IC2-NC_2-Pad8)") (class "Default")
      (node (ref "IC2") (pin "8") (pinfunction "NC_2_8") (pintype "bidirectional"))
    )
    (net (code "66") (name "unconnected-(IC3-NC-Pad46)") (class "Default")
      (node (ref "IC3") (pin "46") (pinfunction "NC_46") (pintype "no_connect"))
    )
    (net (code "67") (name "unconnected-(IC3-NSHDN-Pad48)") (class "Default")
      (node (ref "IC3") (pin "48") (pinfunction "NSHDN_48") (pintype "bidirectional"))
    )
    (net (code "68") (name "unconnected-(U$3-NC-PadNC1)") (class "Default")
      (node (ref "U$3") (pin "NC1") (pinfunction "NC_NC1") (pintype "no_connect"))
    )
    (net (code "69") (name "unconnected-(U$3-NC-PadNC2)") (class "Default")
      (node (ref "U$3") (pin "NC2") (pinfunction "NC_NC2") (pintype "no_connect"))
    )
  )
)
